# cc_power_supply.net
KiCad netlist of a schematic drawn in EAGLE
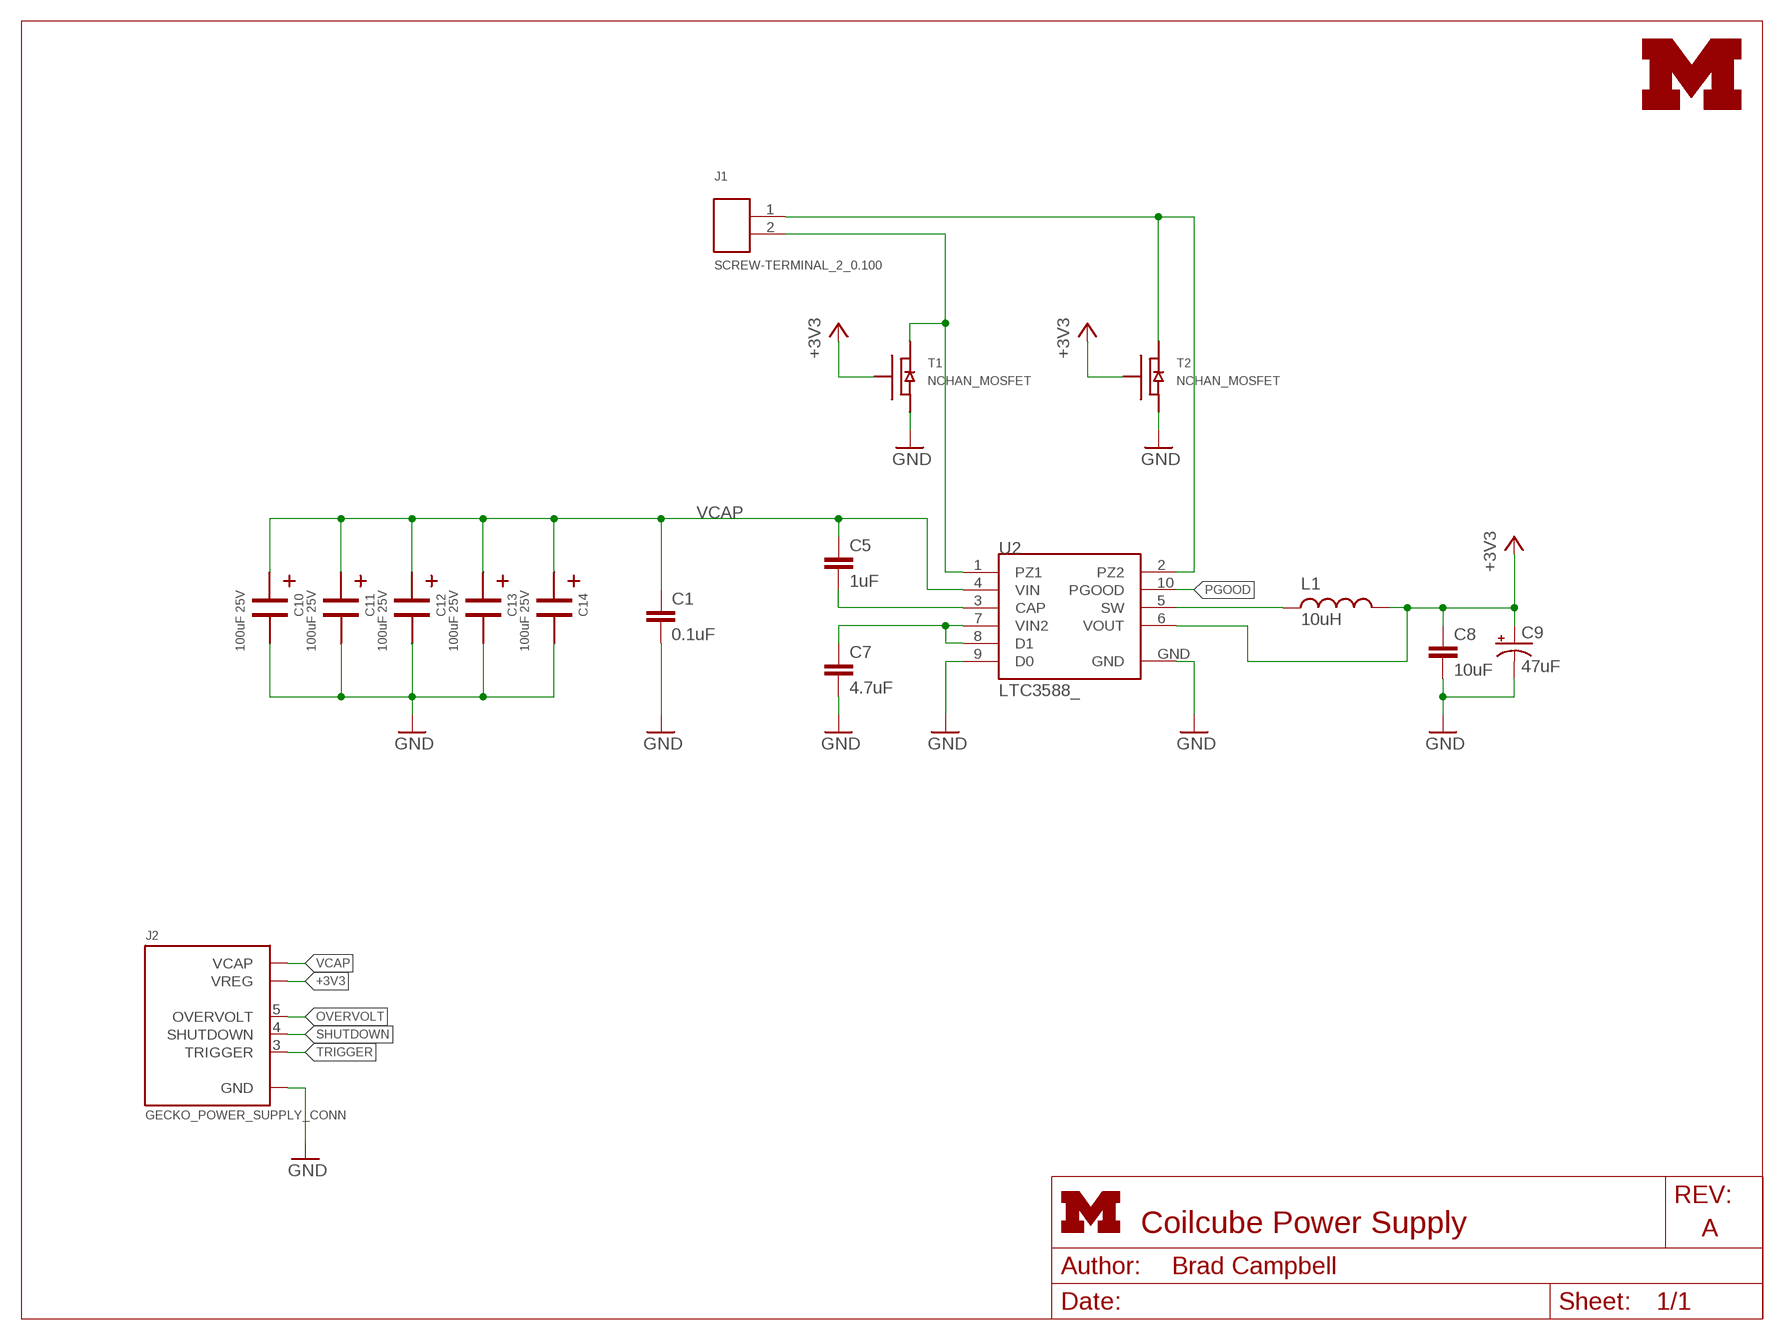
[diagram p0: schematic, sheet 1]

(export (version "E")
  (design (tool "Eeschema 10.0.6"))
  (components
    (comp (ref "C1")
      (value "0.1uF")
      (footprint "eagle-import:C0603")
      (libsource (lib "eagle-import") (part "C-EUC0603"))
    )
    (comp (ref "C5")
      (value "1uF")
      (footprint "eagle-import:C0603")
      (libsource (lib "eagle-import") (part "C-EUC0603"))
    )
    (comp (ref "C7")
      (value "4.7uF")
      (footprint "eagle-import:C0603")
      (libsource (lib "eagle-import") (part "C-EUC0603"))
    )
    (comp (ref "C8")
      (value "10uF")
      (footprint "eagle-import:C1206")
      (libsource (lib "eagle-import") (part "C-EUC1206"))
    )
    (comp (ref "C9")
      (value "47uF")
      (footprint "eagle-import:EIA3216")
      (libsource (lib "eagle-import") (part "CAP_POL1206"))
    )
    (comp (ref "C10")
      (value "100uF 25V")
      (footprint "eagle-import:2917_CAP_POL")
      (libsource (lib "eagle-import") (part "2917_CAP_POL"))
    )
    (comp (ref "C11")
      (value "100uF 25V")
      (footprint "eagle-import:2917_CAP_POL")
      (libsource (lib "eagle-import") (part "2917_CAP_POL"))
    )
    (comp (ref "C12")
      (value "100uF 25V")
      (footprint "eagle-import:2917_CAP_POL")
      (libsource (lib "eagle-import") (part "2917_CAP_POL"))
    )
    (comp (ref "C13")
      (value "100uF 25V")
      (footprint "eagle-import:2917_CAP_POL")
      (libsource (lib "eagle-import") (part "2917_CAP_POL"))
    )
    (comp (ref "C14")
      (value "100uF 25V")
      (footprint "eagle-import:2917_CAP_POL")
      (libsource (lib "eagle-import") (part "2917_CAP_POL"))
    )
    (comp (ref "J1")
      (value "SCREW-TERMINAL_2_0.100")
      (footprint "eagle-import:CONN_BLOCK_2")
      (libsource (lib "eagle-import") (part "SCREW-TERMINAL_2_0.100"))
    )
    (comp (ref "J2")
      (value "GECKO_POWER_SUPPLY_CONN")
      (footprint "eagle-import:HEADER1X6_0.05IN")
      (libsource (lib "eagle-import") (part "GECKO_POWER_SUPPLY_CONN"))
    )
    (comp (ref "L1")
      (value "10uH")
      (footprint "eagle-import:1210")
      (libsource (lib "eagle-import") (part "INDUCTOR1210"))
    )
    (comp (ref "T1")
      (value "NCHAN_MOSFET")
      (footprint "eagle-import:NCHAN_MOSFET")
      (libsource (lib "eagle-import") (part "NCHAN_MOSFET"))
    )
    (comp (ref "T2")
      (value "NCHAN_MOSFET")
      (footprint "eagle-import:NCHAN_MOSFET")
      (libsource (lib "eagle-import") (part "NCHAN_MOSFET"))
    )
    (comp (ref "U$2")
      (value "UMICH_SOLID_SMALL")
      (footprint "eagle-import:UMICH_SOLID_75MIL")
      (libsource (lib "eagle-import") (part "UMICH_SOLID_SMALL"))
    )
    (comp (ref "U2")
      (value "LTC3588_")
      (footprint "eagle-import:MSOP-10-GNDPAD")
      (libsource (lib "eagle-import") (part "LTC3588_"))
    )
  )
  (nets
    (net (code "1") (name "+3V3") (class "Default")
      (node (ref "C8") (pin "1") (pinfunction "1_1") (pintype "passive"))
      (node (ref "C9") (pin "A") (pinfunction "+_A") (pintype "passive"))
      (node (ref "J2") (pin "2") (pinfunction "VREG_2") (pintype "bidirectional"))
      (node (ref "L1") (pin "2") (pinfunction "2_2") (pintype "passive"))
      (node (ref "T1") (pin "G") (pinfunction "G_G") (pintype "bidirectional"))
      (node (ref "T2") (pin "G") (pinfunction "G_G") (pintype "bidirectional"))
      (node (ref "U2") (pin "6") (pinfunction "VOUT_6") (pintype "bidirectional"))
    )
    (net (code "2") (name "GND") (class "Default")
      (node (ref "C1") (pin "2") (pinfunction "2_2") (pintype "passive"))
      (node (ref "C10") (pin "-") (pinfunction "-_-") (pintype "bidirectional"))
      (node (ref "C11") (pin "-") (pinfunction "-_-") (pintype "bidirectional"))
      (node (ref "C12") (pin "-") (pinfunction "-_-") (pintype "bidirectional"))
      (node (ref "C13") (pin "-") (pinfunction "-_-") (pintype "bidirectional"))
      (node (ref "C14") (pin "-") (pinfunction "-_-") (pintype "bidirectional"))
      (node (ref "C7") (pin "2") (pinfunction "2_2") (pintype "passive"))
      (node (ref "C8") (pin "2") (pinfunction "2_2") (pintype "passive"))
      (node (ref "C9") (pin "C") (pinfunction "-_C") (pintype "passive"))
      (node (ref "J2") (pin "1") (pinfunction "GND_1") (pintype "bidirectional"))
      (node (ref "T1") (pin "S") (pinfunction "S_S") (pintype "bidirectional"))
      (node (ref "T2") (pin "S") (pinfunction "S_S") (pintype "bidirectional"))
      (node (ref "U2") (pin "9") (pinfunction "D0_9") (pintype "bidirectional"))
      (node (ref "U2") (pin "GND") (pinfunction "GND_GND") (pintype "bidirectional"))
    )
    (net (code "3") (name "Net-(U2-CAP)") (class "Default")
      (node (ref "C5") (pin "2") (pinfunction "2_2") (pintype "passive"))
      (node (ref "U2") (pin "3") (pinfunction "CAP_3") (pintype "bidirectional"))
    )
    (net (code "4") (name "Net-(U2-D1)") (class "Default")
      (node (ref "C7") (pin "1") (pinfunction "1_1") (pintype "passive"))
      (node (ref "U2") (pin "7") (pinfunction "VIN2_7") (pintype "bidirectional"))
      (node (ref "U2") (pin "8") (pinfunction "D1_8") (pintype "bidirectional"))
    )
    (net (code "5") (name "Net-(U2-PZ1)") (class "Default")
      (node (ref "J1") (pin "2") (pinfunction "2_2") (pintype "bidirectional"))
      (node (ref "T1") (pin "D") (pinfunction "D_D") (pintype "bidirectional"))
      (node (ref "U2") (pin "1") (pinfunction "PZ1_1") (pintype "bidirectional"))
    )
    (net (code "6") (name "Net-(U2-PZ2)") (class "Default")
      (node (ref "J1") (pin "1") (pinfunction "1_1") (pintype "bidirectional"))
      (node (ref "T2") (pin "D") (pinfunction "D_D") (pintype "bidirectional"))
      (node (ref "U2") (pin "2") (pinfunction "PZ2_2") (pintype "bidirectional"))
    )
    (net (code "7") (name "Net-(U2-SW)") (class "Default")
      (node (ref "L1") (pin "1") (pinfunction "1_1") (pintype "passive"))
      (node (ref "U2") (pin "5") (pinfunction "SW_5") (pintype "bidirectional"))
    )
    (net (code "8") (name "OVERVOLT") (class "Default")
      (node (ref "J2") (pin "5") (pinfunction "OVERVOLT_5") (pintype "bidirectional"))
    )
    (net (code "9") (name "PGOOD") (class "Default")
      (node (ref "U2") (pin "10") (pinfunction "PGOOD_10") (pintype "bidirectional"))
    )
    (net (code "10") (name "SHUTDOWN") (class "Default")
      (node (ref "J2") (pin "4") (pinfunction "SHUTDOWN_4") (pintype "bidirectional"))
    )
    (net (code "11") (name "TRIGGER") (class "Default")
      (node (ref "J2") (pin "3") (pinfunction "TRIGGER_3") (pintype "bidirectional"))
    )
    (net (code "12") (name "VCAP") (class "Default")
      (node (ref "C1") (pin "1") (pinfunction "1_1") (pintype "passive"))
      (node (ref "C10") (pin "+") (pinfunction "+_+") (pintype "bidirectional"))
      (node (ref "C11") (pin "+") (pinfunction "+_+") (pintype "bidirectional"))
      (node (ref "C12") (pin "+") (pinfunction "+_+") (pintype "bidirectional"))
      (node (ref "C13") (pin "+") (pinfunction "+_+") (pintype "bidirectional"))
      (node (ref "C14") (pin "+") (pinfunction "+_+") (pintype "bidirectional"))
      (node (ref "C5") (pin "1") (pinfunction "1_1") (pintype "passive"))
      (node (ref "J2") (pin "6") (pinfunction "VCAP_6") (pintype "output"))
      (node (ref "U2") (pin "4") (pinfunction "VIN_4") (pintype "bidirectional"))
    )
  )
)
